# design.net
KiCad netlist of a schematic drawn in Altium Designer
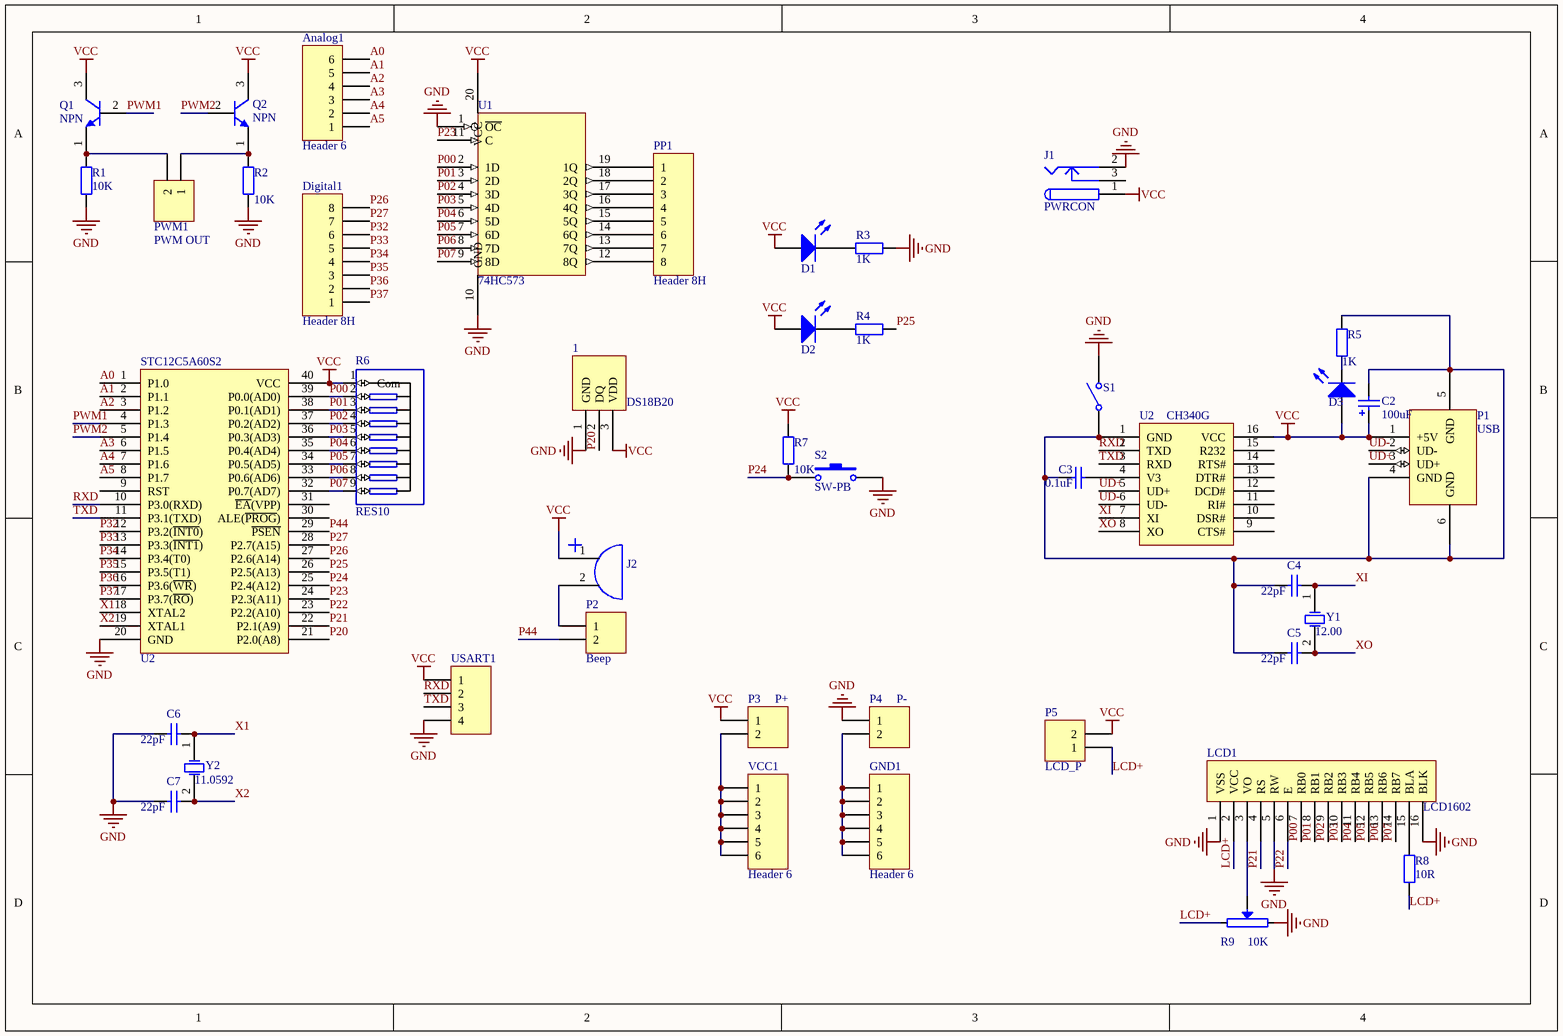
[diagram p0: 主控板电路.SchDoc]

(export (version "E")
  (design (tool "Eeschema 10.0.6"))
  (components
    (comp (ref "1")
      (value "DS18B20")
      (footprint "TO-92A")
      (description "温度传感器")
      (libsource (lib "fszhang") (part "DS18B20"))
    )
    (comp (ref "Analog1")
      (value "Header 6")
      (footprint "HDR1X6")
      (description "Header, 6-Pin")
      (fields (field (name "PUBLISHER") "Altium Limited"))
      (libsource (lib "Miscellaneous Connectors") (part "Header 6"))
    )
    (comp (ref "C2")
      (value "100uF")
      (footprint "RB.1/.3")
      (description "Polarized Capacitor (Axial)")
      (fields (field (name "Comment") "Cap Pol2") (field (name "PUBLISHER") "Altium Limited"))
      (libsource (lib "Miscellaneous Devices") (part "Cap Pol2"))
    )
    (comp (ref "C3")
      (value "0.1uF")
      (footprint "CAPR5-4X5")
      (description "Capacitor (Semiconductor SIM Model)")
      (fields (field (name "Comment") "Cap Semi") (field (name "PUBLISHER") "Altium Limited"))
      (libsource (lib "Miscellaneous Devices") (part "Cap Semi"))
    )
    (comp (ref "C4")
      (value "22pF")
      (footprint "CAPR5-4X5")
      (description "Capacitor (Semiconductor SIM Model)")
      (fields (field (name "Comment") "Cap Semi") (field (name "PUBLISHER") "Altium Limited"))
      (libsource (lib "Miscellaneous Devices") (part "Cap Semi"))
    )
    (comp (ref "C5")
      (value "22pF")
      (footprint "CAPR5-4X5")
      (description "Capacitor (Semiconductor SIM Model)")
      (fields (field (name "Comment") "Cap Semi") (field (name "PUBLISHER") "Altium Limited"))
      (libsource (lib "Miscellaneous Devices") (part "Cap Semi"))
    )
    (comp (ref "C6")
      (value "22pF")
      (footprint "CAPR5-4X5")
      (description "Capacitor (Semiconductor SIM Model)")
      (fields (field (name "Comment") "Cap Semi") (field (name "PUBLISHER") "Altium Limited"))
      (libsource (lib "Miscellaneous Devices") (part "Cap Semi"))
    )
    (comp (ref "C7")
      (value "22pF")
      (footprint "CAPR5-4X5")
      (description "Capacitor (Semiconductor SIM Model)")
      (fields (field (name "Comment") "Cap Semi") (field (name "PUBLISHER") "Altium Limited"))
      (libsource (lib "Miscellaneous Devices") (part "Cap Semi"))
    )
    (comp (ref "D1")
      (value "LED0")
      (footprint "LED_A2")
      (description "发光二极管")
      (fields (field (name "PUBLISHER") "Altium Limited"))
      (libsource (lib "fszhang") (part "LED0"))
    )
    (comp (ref "D2")
      (value "LED0")
      (footprint "LED_A2")
      (description "发光二极管")
      (fields (field (name "PUBLISHER") "Altium Limited"))
      (libsource (lib "fszhang") (part "LED0"))
    )
    (comp (ref "D3")
      (value "LED0")
      (footprint "LED_A2")
      (description "发光二极管")
      (fields (field (name "PUBLISHER") "Altium Limited"))
      (libsource (lib "fszhang") (part "LED0"))
    )
    (comp (ref "Digital1")
      (value "Header 8H")
      (footprint "HDR1X8")
      (description "Header, 8-Pin, Right Angle")
      (fields (field (name "PUBLISHER") "Altium Limited"))
      (libsource (lib "") (part "Header 8H_1"))
    )
    (comp (ref "GND1")
      (value "Header 6")
      (footprint "HDR1X6")
      (description "Header, 6-Pin")
      (fields (field (name "PUBLISHER") "Altium Limited"))
      (libsource (lib "") (part "Header 6_1"))
    )
    (comp (ref "J1")
      (value "PWRCON")
      (footprint "DC-005")
      (description "直流电源端子")
      (fields (field (name "PUBLISHER") "Altium Limited"))
      (libsource (lib "HDR_fszhang") (part "PWRCON"))
    )
    (comp (ref "J2")
      (value "BEEP-S")
      (footprint "BEEP-S")
      (description "有源蜂鸣器")
      (libsource (lib "fszhang") (part "BEEP-S"))
    )
    (comp (ref "LCD1") (value "LCD1602") (footprint "HDR1X16") (libsource (lib "液晶") (part "LCD1602")))
    (comp (ref "P1")
      (value "USB")
      (footprint "USB")
      (description "USB Port")
      (libsource (lib "CHXXXSCH") (part "USB"))
    )
    (comp (ref "P2")
      (value "Beep")
      (footprint "HDR1X2")
      (description "Header, 2-Pin")
      (fields (field (name "PUBLISHER") "Altium Limited"))
      (libsource (lib "Miscellaneous Connectors") (part "Header 2"))
    )
    (comp (ref "P3")
      (value "P+")
      (footprint "HDR1X2")
      (description "Header, 2-Pin")
      (fields (field (name "PUBLISHER") "Altium Limited"))
      (libsource (lib "Miscellaneous Connectors") (part "Header 2"))
    )
    (comp (ref "P4")
      (value "P-")
      (footprint "HDR1X2")
      (description "Header, 2-Pin")
      (fields (field (name "PUBLISHER") "Altium Limited"))
      (libsource (lib "Miscellaneous Connectors") (part "Header 2"))
    )
    (comp (ref "P5")
      (value "LCD_P")
      (footprint "HDR1X2")
      (description "Header, 2-Pin")
      (fields (field (name "PUBLISHER") "Altium Limited"))
      (libsource (lib "") (part "Header 2_2"))
    )
    (comp (ref "PP1")
      (value "Header 8H")
      (footprint "HDR1X8")
      (description "Header, 8-Pin, Right Angle")
      (fields (field (name "PUBLISHER") "Altium Limited"))
      (libsource (lib "Miscellaneous Connectors") (part "Header 8H"))
    )
    (comp (ref "PWM1")
      (value "PWM OUT")
      (footprint "HDR1X2")
      (description "Header, 2-Pin")
      (fields (field (name "PUBLISHER") "Altium Limited"))
      (libsource (lib "") (part "Header 2_1"))
    )
    (comp (ref "Q1")
      (value "NPN")
      (footprint "TO-92A")
      (description "三极管")
      (fields (field (name "PUBLISHER") "Altium Limited"))
      (libsource (lib "fszhang") (part "NPN2"))
    )
    (comp (ref "Q2")
      (value "NPN")
      (footprint "TO-92A")
      (description "三极管")
      (fields (field (name "PUBLISHER") "Altium Limited"))
      (libsource (lib "fszhang") (part "NPN2"))
    )
    (comp (ref "R1")
      (value "10K")
      (footprint "AXIAL-0.4")
      (description "Resistor")
      (fields (field (name "Comment") "Res2") (field (name "PUBLISHER") "Altium Limited"))
      (libsource (lib "") (part "Res2_1"))
    )
    (comp (ref "R2")
      (value "10K")
      (footprint "AXIAL-0.4")
      (description "Resistor")
      (fields (field (name "Comment") "Res2") (field (name "PUBLISHER") "Altium Limited"))
      (libsource (lib "Miscellaneous Devices") (part "Res2"))
    )
    (comp (ref "R3")
      (value "1K")
      (footprint "AXIAL-0.4")
      (description "Resistor")
      (fields (field (name "Comment") "Res2") (field (name "PUBLISHER") "Altium Limited"))
      (libsource (lib "") (part "Res2_2"))
    )
    (comp (ref "R4")
      (value "1K")
      (footprint "AXIAL-0.4")
      (description "Resistor")
      (fields (field (name "Comment") "Res2") (field (name "PUBLISHER") "Altium Limited"))
      (libsource (lib "") (part "Res2_2"))
    )
    (comp (ref "R5")
      (value "1K")
      (footprint "AXIAL-0.4")
      (description "Resistor")
      (fields (field (name "Comment") "Res2") (field (name "PUBLISHER") "Altium Limited"))
      (libsource (lib "Miscellaneous Devices") (part "Res2"))
    )
    (comp (ref "R6") (value "RES10") (footprint "SIP9") (libsource (lib "电阻") (part "RES10")))
    (comp (ref "R7")
      (value "10K")
      (footprint "AXIAL-0.4")
      (description "Resistor")
      (fields (field (name "Comment") "Res2") (field (name "PUBLISHER") "Altium Limited"))
      (libsource (lib "Miscellaneous Devices") (part "Res2"))
    )
    (comp (ref "R8")
      (value "10R")
      (footprint "AXIAL-0.4")
      (description "Resistor")
      (fields (field (name "Comment") "Res2") (field (name "PUBLISHER") "Altium Limited"))
      (libsource (lib "Miscellaneous Devices") (part "Res2"))
    )
    (comp (ref "R9") (value "10K") (footprint "RVR-2") (libsource (lib "常用元件库") (part "VR")))
    (comp (ref "S1")
      (value "SW-SPST")
      (footprint "SWITCH_B1")
      (description "Single-Pole, Single-Throw Switch")
      (fields (field (name "PUBLISHER") "Altium Limited"))
      (libsource (lib "Miscellaneous Devices") (part "SW-SPST"))
    )
    (comp (ref "S2")
      (value "SW-PB")
      (footprint "SW-80")
      (description "Switch")
      (fields (field (name "PUBLISHER") "Altium Limited"))
      (libsource (lib "Miscellaneous Devices") (part "SW-PB"))
    )
    (comp (ref "STC12C5A60S2") (value "U2") (footprint "DIP-40") (libsource (lib "51单片机") (part "89C51")))
    (comp (ref "U1") (value "74HC573") (footprint "DIP-20") (libsource (lib "TTL74系列IC") (part "74HC573")))
    (comp (ref "U2")
      (value "CH340G")
      (footprint "SOIC127P600X170-16N")
      (libsource (lib "CH340G") (part "Component_1"))
    )
    (comp (ref "USART1")
      (value "Header 4")
      (footprint "HDR1X4")
      (description "Header, 4-Pin")
      (fields (field (name "PUBLISHER") "Altium Limited"))
      (libsource (lib "Miscellaneous Connectors") (part "Header 4"))
    )
    (comp (ref "VCC1")
      (value "Header 6")
      (footprint "HDR1X6")
      (description "Header, 6-Pin")
      (fields (field (name "PUBLISHER") "Altium Limited"))
      (libsource (lib "") (part "Header 6_1"))
    )
    (comp (ref "Y1")
      (value "12.00")
      (footprint "XTAL")
      (description "Crystal Oscillator")
      (fields (field (name "Comment") "XTAL") (field (name "PUBLISHER") "Altium Limited"))
      (libsource (lib "Miscellaneous Devices") (part "XTAL"))
    )
    (comp (ref "Y2")
      (value "11.0592")
      (footprint "XTAL")
      (description "Crystal Oscillator")
      (fields (field (name "Comment") "XTAL") (field (name "PUBLISHER") "Altium Limited"))
      (libsource (lib "Miscellaneous Devices") (part "XTAL"))
    )
  )
  (nets
    (net (code "1") (name "/A0") (class "Default")
      (node (ref "Analog1") (pin "6") (pinfunction "6_6") (pintype "passive"))
      (node (ref "STC12C5A60S2") (pin "1") (pinfunction "P1.0_1") (pintype "passive"))
    )
    (net (code "2") (name "/A1") (class "Default")
      (node (ref "Analog1") (pin "5") (pinfunction "5_5") (pintype "passive"))
      (node (ref "STC12C5A60S2") (pin "2") (pinfunction "P1.1_2") (pintype "passive"))
    )
    (net (code "3") (name "/A2") (class "Default")
      (node (ref "Analog1") (pin "4") (pinfunction "4_4") (pintype "passive"))
      (node (ref "STC12C5A60S2") (pin "3") (pinfunction "P1.2_3") (pintype "passive"))
    )
    (net (code "4") (name "/A3") (class "Default")
      (node (ref "Analog1") (pin "3") (pinfunction "3_3") (pintype "passive"))
      (node (ref "STC12C5A60S2") (pin "6") (pinfunction "P1.5_6") (pintype "passive"))
    )
    (net (code "5") (name "/A4") (class "Default")
      (node (ref "Analog1") (pin "2") (pinfunction "2_2") (pintype "passive"))
      (node (ref "STC12C5A60S2") (pin "7") (pinfunction "P1.6_7") (pintype "passive"))
    )
    (net (code "6") (name "/A5") (class "Default")
      (node (ref "Analog1") (pin "1") (pinfunction "1_1") (pintype "passive"))
      (node (ref "STC12C5A60S2") (pin "8") (pinfunction "P1.7_8") (pintype "passive"))
    )
    (net (code "7") (name "/LCD+") (class "Default")
      (node (ref "LCD1") (pin "2") (pinfunction "VCC_2") (pintype "passive"))
      (node (ref "P5") (pin "1") (pinfunction "1_1") (pintype "passive"))
      (node (ref "R8") (pin "1") (pinfunction "1_1") (pintype "passive"))
      (node (ref "R9") (pin "1") (pintype "passive"))
    )
    (net (code "8") (name "/P00") (class "Default")
      (node (ref "LCD1") (pin "7") (pinfunction "RB0_7") (pintype "passive"))
      (node (ref "R6") (pin "2") (pinfunction "2_2") (pintype "bidirectional"))
      (node (ref "STC12C5A60S2") (pin "39") (pinfunction "P0.0(AD0)_39") (pintype "passive"))
      (node (ref "U1") (pin "2") (pinfunction "1D_2") (pintype "input"))
    )
    (net (code "9") (name "/P01") (class "Default")
      (node (ref "LCD1") (pin "8") (pinfunction "RB1_8") (pintype "passive"))
      (node (ref "R6") (pin "3") (pinfunction "3_3") (pintype "bidirectional"))
      (node (ref "STC12C5A60S2") (pin "38") (pinfunction "P0.1(AD1)_38") (pintype "passive"))
      (node (ref "U1") (pin "3") (pinfunction "2D_3") (pintype "input"))
    )
    (net (code "10") (name "/P02") (class "Default")
      (node (ref "LCD1") (pin "9") (pinfunction "RB2_9") (pintype "passive"))
      (node (ref "R6") (pin "4") (pinfunction "4_4") (pintype "bidirectional"))
      (node (ref "STC12C5A60S2") (pin "37") (pinfunction "P0.2(AD2)_37") (pintype "passive"))
      (node (ref "U1") (pin "4") (pinfunction "3D_4") (pintype "input"))
    )
    (net (code "11") (name "/P03") (class "Default")
      (node (ref "LCD1") (pin "10") (pinfunction "RB3_10") (pintype "passive"))
      (node (ref "R6") (pin "5") (pinfunction "5_5") (pintype "bidirectional"))
      (node (ref "STC12C5A60S2") (pin "36") (pinfunction "P0.3(AD3)_36") (pintype "passive"))
      (node (ref "U1") (pin "5") (pinfunction "4D_5") (pintype "input"))
    )
    (net (code "12") (name "/P04") (class "Default")
      (node (ref "LCD1") (pin "11") (pinfunction "RB4_11") (pintype "passive"))
      (node (ref "R6") (pin "6") (pinfunction "6_6") (pintype "bidirectional"))
      (node (ref "STC12C5A60S2") (pin "35") (pinfunction "P0.4(AD4)_35") (pintype "passive"))
      (node (ref "U1") (pin "6") (pinfunction "5D_6") (pintype "input"))
    )
    (net (code "13") (name "/P05") (class "Default")
      (node (ref "LCD1") (pin "12") (pinfunction "RB5_12") (pintype "passive"))
      (node (ref "R6") (pin "7") (pinfunction "7_7") (pintype "bidirectional"))
      (node (ref "STC12C5A60S2") (pin "34") (pinfunction "P0.5(AD5)_34") (pintype "passive"))
      (node (ref "U1") (pin "7") (pinfunction "6D_7") (pintype "input"))
    )
    (net (code "14") (name "/P06") (class "Default")
      (node (ref "LCD1") (pin "13") (pinfunction "RB6_13") (pintype "passive"))
      (node (ref "R6") (pin "8") (pinfunction "8_8") (pintype "bidirectional"))
      (node (ref "STC12C5A60S2") (pin "33") (pinfunction "P0.6(AD6)_33") (pintype "passive"))
      (node (ref "U1") (pin "8") (pinfunction "7D_8") (pintype "input"))
    )
    (net (code "15") (name "/P07") (class "Default")
      (node (ref "LCD1") (pin "14") (pinfunction "RB7_14") (pintype "passive"))
      (node (ref "R6") (pin "9") (pinfunction "9_9") (pintype "bidirectional"))
      (node (ref "STC12C5A60S2") (pin "32") (pinfunction "P0.7(AD7)_32") (pintype "passive"))
      (node (ref "U1") (pin "9") (pinfunction "8D_9") (pintype "input"))
    )
    (net (code "16") (name "/P20") (class "Default")
      (node (ref "1") (pin "2") (pinfunction "DQ_2") (pintype "passive"))
      (node (ref "STC12C5A60S2") (pin "21") (pinfunction "P2.0(A8)_21") (pintype "passive"))
    )
    (net (code "17") (name "/P21") (class "Default")
      (node (ref "LCD1") (pin "4") (pinfunction "RS_4") (pintype "passive"))
      (node (ref "STC12C5A60S2") (pin "22") (pinfunction "P2.1(A9)_22") (pintype "passive"))
    )
    (net (code "18") (name "/P22") (class "Default")
      (node (ref "LCD1") (pin "6") (pinfunction "E_6") (pintype "passive"))
      (node (ref "STC12C5A60S2") (pin "23") (pinfunction "P2.2(A10)_23") (pintype "passive"))
    )
    (net (code "19") (name "/P23") (class "Default")
      (node (ref "STC12C5A60S2") (pin "24") (pinfunction "P2.3(A11)_24") (pintype "passive"))
      (node (ref "U1") (pin "11") (pinfunction "C_11") (pintype "input"))
    )
    (net (code "20") (name "/P24") (class "Default")
      (node (ref "R7") (pin "1") (pinfunction "1_1") (pintype "passive"))
      (node (ref "S2") (pin "1") (pinfunction "1_1") (pintype "passive"))
      (node (ref "STC12C5A60S2") (pin "25") (pinfunction "P2.4(A12)_25") (pintype "passive"))
    )
    (net (code "21") (name "/P25") (class "Default")
      (node (ref "R4") (pin "1") (pinfunction "1_1") (pintype "passive"))
      (node (ref "STC12C5A60S2") (pin "26") (pinfunction "P2.5(A13)_26") (pintype "passive"))
    )
    (net (code "22") (name "/P26") (class "Default")
      (node (ref "Digital1") (pin "8") (pinfunction "8_8") (pintype "passive"))
      (node (ref "STC12C5A60S2") (pin "27") (pinfunction "P2.6(A14)_27") (pintype "passive"))
    )
    (net (code "23") (name "/P27") (class "Default")
      (node (ref "Digital1") (pin "7") (pinfunction "7_7") (pintype "passive"))
      (node (ref "STC12C5A60S2") (pin "28") (pinfunction "P2.7(A15)_28") (pintype "passive"))
    )
    (net (code "24") (name "/P32") (class "Default")
      (node (ref "Digital1") (pin "6") (pinfunction "6_6") (pintype "passive"))
      (node (ref "STC12C5A60S2") (pin "12") (pinfunction "P3.2(~{INT0})_12") (pintype "passive"))
    )
    (net (code "25") (name "/P33") (class "Default")
      (node (ref "Digital1") (pin "5") (pinfunction "5_5") (pintype "passive"))
      (node (ref "STC12C5A60S2") (pin "13") (pinfunction "P3.3(~{INT1})_13") (pintype "passive"))
    )
    (net (code "26") (name "/P34") (class "Default")
      (node (ref "Digital1") (pin "4") (pinfunction "4_4") (pintype "passive"))
      (node (ref "STC12C5A60S2") (pin "14") (pinfunction "P3.4(T0)_14") (pintype "passive"))
    )
    (net (code "27") (name "/P35") (class "Default")
      (node (ref "Digital1") (pin "3") (pinfunction "3_3") (pintype "passive"))
      (node (ref "STC12C5A60S2") (pin "15") (pinfunction "P3.5(T1)_15") (pintype "passive"))
    )
    (net (code "28") (name "/P36") (class "Default")
      (node (ref "Digital1") (pin "2") (pinfunction "2_2") (pintype "passive"))
      (node (ref "STC12C5A60S2") (pin "16") (pinfunction "P3.6(~{WR})_16") (pintype "passive"))
    )
    (net (code "29") (name "/P37") (class "Default")
      (node (ref "Digital1") (pin "1") (pinfunction "1_1") (pintype "passive"))
      (node (ref "STC12C5A60S2") (pin "17") (pinfunction "P3.7(~{RO})_17") (pintype "passive"))
    )
    (net (code "30") (name "/P44") (class "Default")
      (node (ref "P2") (pin "2") (pinfunction "2_2") (pintype "passive"))
      (node (ref "STC12C5A60S2") (pin "29") (pinfunction "~{PSEN}_29") (pintype "passive"))
    )
    (net (code "31") (name "/PWM1") (class "Default")
      (node (ref "Q1") (pin "2") (pinfunction "B_2") (pintype "passive"))
      (node (ref "STC12C5A60S2") (pin "4") (pinfunction "P1.3_4") (pintype "passive"))
    )
    (net (code "32") (name "/PWM2") (class "Default")
      (node (ref "Q2") (pin "2") (pinfunction "B_2") (pintype "passive"))
      (node (ref "STC12C5A60S2") (pin "5") (pinfunction "P1.4_5") (pintype "passive"))
    )
    (net (code "33") (name "/RXD") (class "Default")
      (node (ref "STC12C5A60S2") (pin "10") (pinfunction "P3.0(RXD)_10") (pintype "passive"))
      (node (ref "U2") (pin "2") (pinfunction "TXD_2") (pintype "passive"))
      (node (ref "USART1") (pin "2") (pinfunction "2_2") (pintype "passive"))
    )
    (net (code "34") (name "/TXD") (class "Default")
      (node (ref "STC12C5A60S2") (pin "11") (pinfunction "P3.1(TXD)_11") (pintype "passive"))
      (node (ref "U2") (pin "3") (pinfunction "RXD_3") (pintype "passive"))
      (node (ref "USART1") (pin "3") (pinfunction "3_3") (pintype "passive"))
    )
    (net (code "35") (name "/UD+") (class "Default")
      (node (ref "P1") (pin "3") (pinfunction "UD+_3") (pintype "bidirectional"))
      (node (ref "U2") (pin "5") (pinfunction "UD+_5") (pintype "passive"))
    )
    (net (code "36") (name "/UD-") (class "Default")
      (node (ref "P1") (pin "2") (pinfunction "UD-_2") (pintype "bidirectional"))
      (node (ref "U2") (pin "6") (pinfunction "UD-_6") (pintype "passive"))
    )
    (net (code "37") (name "/X1") (class "Default")
      (node (ref "C6") (pin "1") (pinfunction "1_1") (pintype "passive"))
      (node (ref "STC12C5A60S2") (pin "18") (pinfunction "XTAL2_18") (pintype "passive"))
      (node (ref "Y2") (pin "1") (pinfunction "OSC1_1") (pintype "passive"))
    )
    (net (code "38") (name "/X2") (class "Default")
      (node (ref "C7") (pin "1") (pinfunction "1_1") (pintype "passive"))
      (node (ref "STC12C5A60S2") (pin "19") (pinfunction "XTAL1_19") (pintype "passive"))
      (node (ref "Y2") (pin "2") (pinfunction "OSC2_2") (pintype "passive"))
    )
    (net (code "39") (name "/XI") (class "Default")
      (node (ref "C4") (pin "1") (pinfunction "1_1") (pintype "passive"))
      (node (ref "U2") (pin "7") (pinfunction "XI_7") (pintype "passive"))
      (node (ref "Y1") (pin "1") (pinfunction "OSC1_1") (pintype "passive"))
    )
    (net (code "40") (name "/XO") (class "Default")
      (node (ref "C5") (pin "1") (pinfunction "1_1") (pintype "passive"))
      (node (ref "U2") (pin "8") (pinfunction "XO_8") (pintype "passive"))
      (node (ref "Y1") (pin "2") (pinfunction "OSC2_2") (pintype "passive"))
    )
    (net (code "41") (name "GND") (class "Default")
      (node (ref "1") (pin "1") (pinfunction "GND_1") (pintype "passive"))
      (node (ref "C6") (pin "2") (pinfunction "2_2") (pintype "passive"))
      (node (ref "C7") (pin "2") (pinfunction "2_2") (pintype "passive"))
      (node (ref "J1") (pin "2") (pinfunction "2_2") (pintype "power_in"))
      (node (ref "LCD1") (pin "1") (pinfunction "VSS_1") (pintype "passive"))
      (node (ref "LCD1") (pin "16") (pinfunction "BLK_16") (pintype "passive"))
      (node (ref "LCD1") (pin "5") (pinfunction "RW_5") (pintype "passive"))
      (node (ref "P4") (pin "1") (pinfunction "1_1") (pintype "passive"))
      (node (ref "R1") (pin "1") (pinfunction "1_1") (pintype "passive"))
      (node (ref "R2") (pin "1") (pinfunction "1_1") (pintype "passive"))
      (node (ref "R3") (pin "1") (pinfunction "1_1") (pintype "passive"))
      (node (ref "R9") (pin "2") (pintype "passive"))
      (node (ref "S1") (pin "2") (pinfunction "NO_2") (pintype "passive"))
      (node (ref "S2") (pin "2") (pinfunction "2_2") (pintype "passive"))
      (node (ref "STC12C5A60S2") (pin "20") (pinfunction "GND_20") (pintype "passive"))
      (node (ref "U1") (pin "1") (pinfunction "~{OC}_1") (pintype "input"))
      (node (ref "U1") (pin "10") (pinfunction "GND_10") (pintype "power_in"))
      (node (ref "USART1") (pin "4") (pinfunction "4_4") (pintype "passive"))
    )
    (net (code "42") (name "Net-(D1-K)") (class "Default")
      (node (ref "D1") (pin "2") (pinfunction "K_2") (pintype "passive"))
      (node (ref "R3") (pin "2") (pinfunction "2_2") (pintype "passive"))
    )
    (net (code "43") (name "Net-(D2-K)") (class "Default")
      (node (ref "D2") (pin "2") (pinfunction "K_2") (pintype "passive"))
      (node (ref "R4") (pin "2") (pinfunction "2_2") (pintype "passive"))
    )
    (net (code "44") (name "Net-(D3-K)") (class "Default")
      (node (ref "D3") (pin "2") (pinfunction "K_2") (pintype "passive"))
      (node (ref "R5") (pin "1") (pinfunction "1_1") (pintype "passive"))
    )
    (net (code "45") (name "Net-(GND1-Pad1)") (class "Default")
      (node (ref "GND1") (pin "1") (pinfunction "1_1") (pintype "passive"))
      (node (ref "GND1") (pin "2") (pinfunction "2_2") (pintype "passive"))
      (node (ref "GND1") (pin "3") (pinfunction "3_3") (pintype "passive"))
      (node (ref "GND1") (pin "4") (pinfunction "4_4") (pintype "passive"))
      (node (ref "GND1") (pin "5") (pinfunction "5_5") (pintype "passive"))
      (node (ref "GND1") (pin "6") (pinfunction "6_6") (pintype "passive"))
      (node (ref "P4") (pin "2") (pinfunction "2_2") (pintype "passive"))
    )
    (net (code "46") (name "Net-(J2-1)") (class "Default")
      (node (ref "J2") (pin "2") (pinfunction "1_2") (pintype "passive"))
      (node (ref "P2") (pin "1") (pinfunction "1_1") (pintype "passive"))
    )
    (net (code "47") (name "Net-(LCD1-BLA)") (class "Default")
      (node (ref "LCD1") (pin "15") (pinfunction "BLA_15") (pintype "passive"))
      (node (ref "R8") (pin "2") (pinfunction "2_2") (pintype "passive"))
    )
    (net (code "48") (name "Net-(LCD1-VO)") (class "Default")
      (node (ref "LCD1") (pin "3") (pinfunction "VO_3") (pintype "passive"))
      (node (ref "R9") (pin "W") (pintype "passive"))
    )
    (net (code "49") (name "Net-(P3-Pad2)") (class "Default")
      (node (ref "P3") (pin "2") (pinfunction "2_2") (pintype "passive"))
      (node (ref "VCC1") (pin "1") (pinfunction "1_1") (pintype "passive"))
      (node (ref "VCC1") (pin "2") (pinfunction "2_2") (pintype "passive"))
      (node (ref "VCC1") (pin "3") (pinfunction "3_3") (pintype "passive"))
      (node (ref "VCC1") (pin "4") (pinfunction "4_4") (pintype "passive"))
      (node (ref "VCC1") (pin "5") (pinfunction "5_5") (pintype "passive"))
      (node (ref "VCC1") (pin "6") (pinfunction "6_6") (pintype "passive"))
    )
    (net (code "50") (name "Net-(Q1-E)") (class "Default")
      (node (ref "PWM1") (pin "2") (pinfunction "2_2") (pintype "passive"))
      (node (ref "Q1") (pin "1") (pinfunction "E_1") (pintype "passive"))
      (node (ref "R1") (pin "2") (pinfunction "2_2") (pintype "passive"))
    )
    (net (code "51") (name "Net-(Q2-E)") (class "Default")
      (node (ref "PWM1") (pin "1") (pinfunction "1_1") (pintype "passive"))
      (node (ref "Q2") (pin "1") (pinfunction "E_1") (pintype "passive"))
      (node (ref "R2") (pin "2") (pinfunction "2_2") (pintype "passive"))
    )
    (net (code "52") (name "Net-(S1-COMMON)") (class "Default")
      (node (ref "C2") (pin "2") (pinfunction "2_2") (pintype "passive"))
      (node (ref "C3") (pin "2") (pinfunction "2_2") (pintype "passive"))
      (node (ref "C4") (pin "2") (pinfunction "2_2") (pintype "passive"))
      (node (ref "C5") (pin "2") (pinfunction "2_2") (pintype "passive"))
      (node (ref "P1") (pin "4") (pinfunction "GND_4") (pintype "power_in"))
      (node (ref "P1") (pin "5") (pinfunction "GND_5") (pintype "power_in"))
      (node (ref "P1") (pin "6") (pinfunction "GND_6") (pintype "power_in"))
      (node (ref "R5") (pin "2") (pinfunction "2_2") (pintype "passive"))
      (node (ref "S1") (pin "1") (pinfunction "COMMON_1") (pintype "passive"))
      (node (ref "U2") (pin "1") (pinfunction "GND_1") (pintype "passive"))
    )
    (net (code "53") (name "Net-(U1-1Q)") (class "Default")
      (node (ref "PP1") (pin "1") (pinfunction "1_1") (pintype "passive"))
      (node (ref "U1") (pin "19") (pinfunction "1Q_19") (pintype "output"))
    )
    (net (code "54") (name "Net-(U1-2Q)") (class "Default")
      (node (ref "PP1") (pin "2") (pinfunction "2_2") (pintype "passive"))
      (node (ref "U1") (pin "18") (pinfunction "2Q_18") (pintype "output"))
    )
    (net (code "55") (name "Net-(U1-3Q)") (class "Default")
      (node (ref "PP1") (pin "3") (pinfunction "3_3") (pintype "passive"))
      (node (ref "U1") (pin "17") (pinfunction "3Q_17") (pintype "output"))
    )
    (net (code "56") (name "Net-(U1-4Q)") (class "Default")
      (node (ref "PP1") (pin "4") (pinfunction "4_4") (pintype "passive"))
      (node (ref "U1") (pin "16") (pinfunction "4Q_16") (pintype "output"))
    )
    (net (code "57") (name "Net-(U1-5Q)") (class "Default")
      (node (ref "PP1") (pin "5") (pinfunction "5_5") (pintype "passive"))
      (node (ref "U1") (pin "15") (pinfunction "5Q_15") (pintype "output"))
    )
    (net (code "58") (name "Net-(U1-6Q)") (class "Default")
      (node (ref "PP1") (pin "6") (pinfunction "6_6") (pintype "passive"))
      (node (ref "U1") (pin "14") (pinfunction "6Q_14") (pintype "output"))
    )
    (net (code "59") (name "Net-(U1-7Q)") (class "Default")
      (node (ref "PP1") (pin "7") (pinfunction "7_7") (pintype "passive"))
      (node (ref "U1") (pin "13") (pinfunction "7Q_13") (pintype "output"))
    )
    (net (code "60") (name "Net-(U1-8Q)") (class "Default")
      (node (ref "PP1") (pin "8") (pinfunction "8_8") (pintype "passive"))
      (node (ref "U1") (pin "12") (pinfunction "8Q_12") (pintype "output"))
    )
    (net (code "61") (name "Net-(U2-V3)") (class "Default")
      (node (ref "C3") (pin "1") (pinfunction "1_1") (pintype "passive"))
      (node (ref "U2") (pin "4") (pinfunction "V3_4") (pintype "passive"))
    )
    (net (code "62") (name "VCC") (class "Default")
      (node (ref "1") (pin "3") (pinfunction "VDD_3") (pintype "passive"))
      (node (ref "C2") (pin "1") (pinfunction "1_1") (pintype "passive"))
      (node (ref "D1") (pin "1") (pinfunction "A_1") (pintype "passive"))
      (node (ref "D2") (pin "1") (pinfunction "A_1") (pintype "passive"))
      (node (ref "D3") (pin "1") (pinfunction "A_1") (pintype "passive"))
      (node (ref "J1") (pin "1") (pinfunction "1_1") (pintype "power_in"))
      (node (ref "J2") (pin "1") (pinfunction "0_1") (pintype "passive"))
      (node (ref "P1") (pin "1") (pinfunction "+5V_1") (pintype "power_in"))
      (node (ref "P3") (pin "1") (pinfunction "1_1") (pintype "passive"))
      (node (ref "P5") (pin "2") (pinfunction "2_2") (pintype "passive"))
      (node (ref "Q1") (pin "3") (pinfunction "C_3") (pintype "passive"))
      (node (ref "Q2") (pin "3") (pinfunction "C_3") (pintype "passive"))
      (node (ref "R6") (pin "1") (pinfunction "Com_1") (pintype "bidirectional"))
      (node (ref "R7") (pin "2") (pinfunction "2_2") (pintype "passive"))
      (node (ref "STC12C5A60S2") (pin "40") (pinfunction "VCC_40") (pintype "passive"))
      (node (ref "U1") (pin "20") (pinfunction "VCC_20") (pintype "power_in"))
      (node (ref "U2") (pin "16") (pinfunction "VCC_16") (pintype "passive"))
      (node (ref "USART1") (pin "1") (pinfunction "1_1") (pintype "passive"))
    )
    (net (code "63") (name "unconnected-(J1-Pad3)") (class "Default")
      (node (ref "J1") (pin "3") (pinfunction "3_3") (pintype "power_in"))
    )
    (net (code "64") (name "unconnected-(STC12C5A60S2-ALE(~{PROG})-Pad30)") (class "Default")
      (node (ref "STC12C5A60S2") (pin "30") (pinfunction "ALE(~{PROG})_30") (pintype "passive"))
    )
    (net (code "65") (name "unconnected-(STC12C5A60S2-RST-Pad9)") (class "Default")
      (node (ref "STC12C5A60S2") (pin "9") (pinfunction "RST_9") (pintype "passive"))
    )
    (net (code "66") (name "unconnected-(STC12C5A60S2-~{EA}(VPP)-Pad31)") (class "Default")
      (node (ref "STC12C5A60S2") (pin "31") (pinfunction "~{EA}(VPP)_31") (pintype "passive"))
    )
    (net (code "67") (name "unconnected-(U2-CTS#-Pad9)") (class "Default")
      (node (ref "U2") (pin "9") (pinfunction "CTS#_9") (pintype "passive"))
    )
    (net (code "68") (name "unconnected-(U2-DCD#-Pad12)") (class "Default")
      (node (ref "U2") (pin "12") (pinfunction "DCD#_12") (pintype "passive"))
    )
    (net (code "69") (name "unconnected-(U2-DSR#-Pad10)") (class "Default")
      (node (ref "U2") (pin "10") (pinfunction "DSR#_10") (pintype "passive"))
    )
    (net (code "70") (name "unconnected-(U2-DTR#-Pad13)") (class "Default")
      (node (ref "U2") (pin "13") (pinfunction "DTR#_13") (pintype "passive"))
    )
    (net (code "71") (name "unconnected-(U2-R232-Pad15)") (class "Default")
      (node (ref "U2") (pin "15") (pinfunction "R232_15") (pintype "passive"))
    )
    (net (code "72") (name "unconnected-(U2-RI#-Pad11)") (class "Default")
      (node (ref "U2") (pin "11") (pinfunction "RI#_11") (pintype "passive"))
    )
    (net (code "73") (name "unconnected-(U2-RTS#-Pad14)") (class "Default")
      (node (ref "U2") (pin "14") (pinfunction "RTS#_14") (pintype "passive"))
    )
  )
)
